# HU_SUPPORT_BOARD.net
KiCad netlist of a schematic drawn in Altium Designer
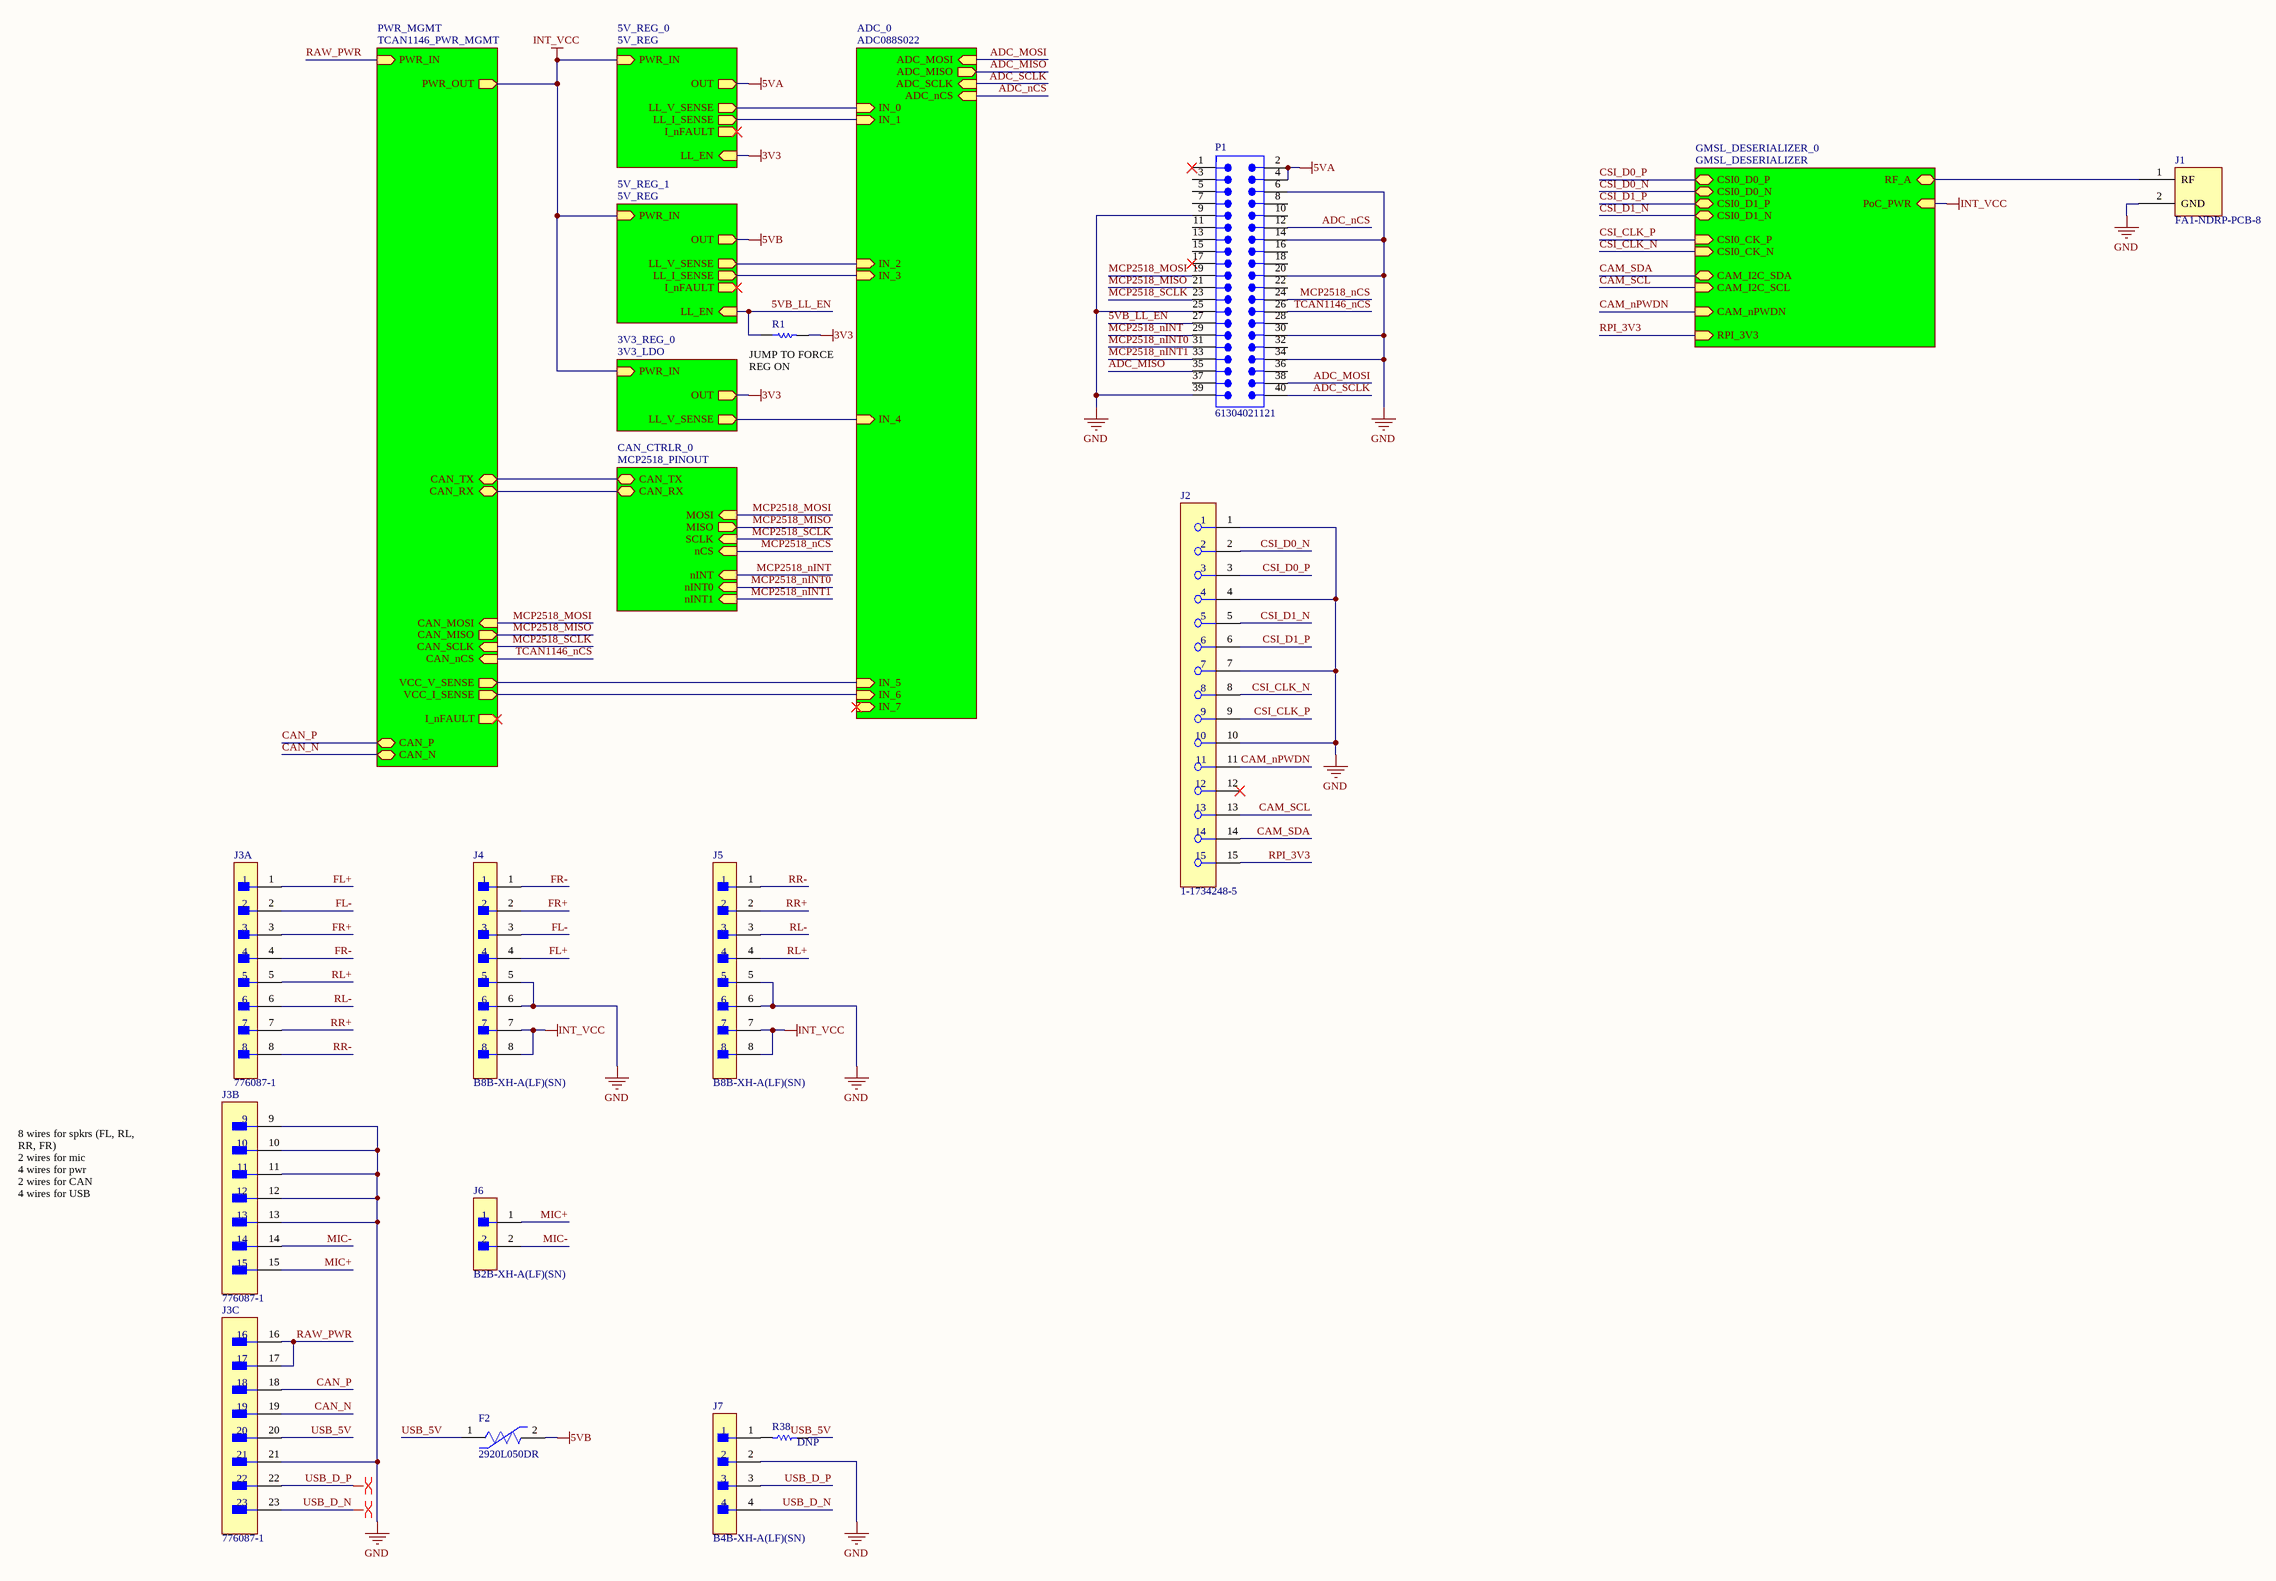
[diagram p0: HU_SUPPORT_BOARD.SchDoc]

(export (version "E")
  (design (tool "Eeschema 10.0.6"))
  (components
    (comp (ref "F2")
      (value "2920L050DR")
      (footprint "FP-2920L050DR-MFG")
      (description "PTC RESET FUSE 60V 500MA 2920")
      (libsource (lib "Altium Content Vault") (part "1c6d77a0208143737455a0c7eb396be"))
    )
    (comp (ref "J1")
      (value "FA1-NDRP-PCB-8")
      (footprint "FA1-NDRP-PCB-8-Footprint-1")
      (description "RF F Connector, Male, Board Mount, Solder Terminal, Plug")
      (libsource (lib "Space Concordia") (part "FA1-NDRP-PCB-8"))
    )
    (comp (ref "J2")
      (value "1-1734248-5")
      (footprint "FP-1-1734248-5-MFG")
      (description "CONN FPC VERT 15POS 1.00MM SMD")
      (fields
        (field (name "MANUFACTURER") "TE")
        (field (name "OCTOPART") "https://octopart.com/1-1734248-5-te+connectivity-40620898")
      )
      (libsource (lib "Altium Content Vault") (part "a0777be16b290adccad2a8f9338c195"))
    )
    (comp (ref "J3")
      (value "776087-1")
      (footprint "FP-776087-1-MFG")
      (description "CONN HEADER R/A 23POS 4MM")
      (libsource (lib "Altium Content Vault") (part "1cdbe6524175775e54446a79a4f0ed8"))
    )
    (comp (ref "J4")
      (value "B8B-XH-A(LF)(SN)")
      (footprint "FP-B8B-XH-A_LF_SN-MFG")
      (description "CONN HEADER VERT 8POS 2.5MM")
      (libsource (lib "Altium Content Vault") (part "99ec2b232beb5d2356d4d77f6a047f0"))
    )
    (comp (ref "J5")
      (value "B8B-XH-A(LF)(SN)")
      (footprint "FP-B8B-XH-A_LF_SN-MFG")
      (description "CONN HEADER VERT 8POS 2.5MM")
      (libsource (lib "Altium Content Vault") (part "99ec2b232beb5d2356d4d77f6a047f0"))
    )
    (comp (ref "J6")
      (value "B2B-XH-A(LF)(SN)")
      (footprint "FP-B2B-XH-A_LF_SN-MFG")
      (description "CONN HEADER VERT 2POS 2.5MM")
      (libsource (lib "Altium Content Vault") (part "3bc925449376181038e59eaffc5286c"))
    )
    (comp (ref "J7")
      (value "B4B-XH-A(LF)(SN)")
      (footprint "FP-B4B-XH-A_LF_SN-MFG")
      (description "CONN HEADER VERT 4POS 2.5MM")
      (libsource (lib "Altium Content Vault") (part "299a8cea1bdcbc3624fe62c390fa72c"))
    )
    (comp (ref "P1")
      (value "61304021121")
      (footprint "61304021121")
      (libsource (lib "Altium Content Vault") (part "Header_Male_2R_40P"))
    )
    (comp (ref "R1")
      (value "DNP")
      (footprint "RESC1005X40X25ML05T05")
      (description "READ THE NAME")
      (libsource (lib "Space Concordia") (part "CMP-009-00206-2"))
    )
    (comp (ref "R38")
      (value "DNP")
      (footprint "R0603B")
      (description "Resistor")
      (libsource (lib "Space Concordia") (part "Resistor"))
    )
  )
  (nets
    (net (code "1") (name "/5VB_LL_EN") (class "Default")
      (node (ref "P1") (pin "27") (pinfunction "27_27") (pintype "passive"))
      (node (ref "R1") (pin "1") (pinfunction "1_1") (pintype "passive"))
    )
    (net (code "2") (name "/ADC_MISO") (class "Default")
      (node (ref "P1") (pin "35") (pinfunction "35_35") (pintype "passive"))
    )
    (net (code "3") (name "/ADC_MOSI") (class "Default")
      (node (ref "P1") (pin "38") (pinfunction "38_38") (pintype "passive"))
    )
    (net (code "4") (name "/ADC_SCLK") (class "Default")
      (node (ref "P1") (pin "40") (pinfunction "40_40") (pintype "passive"))
    )
    (net (code "5") (name "/ADC_nCS") (class "Default")
      (node (ref "P1") (pin "12") (pinfunction "12_12") (pintype "passive"))
    )
    (net (code "6") (name "/CAM_SCL") (class "Default")
      (node (ref "J2") (pin "13") (pinfunction "13_13") (pintype "passive"))
    )
    (net (code "7") (name "/CAM_SDA") (class "Default")
      (node (ref "J2") (pin "14") (pinfunction "14_14") (pintype "passive"))
    )
    (net (code "8") (name "/CAM_nPWDN") (class "Default")
      (node (ref "J2") (pin "11") (pinfunction "11_11") (pintype "passive"))
    )
    (net (code "9") (name "/CAN_N") (class "Default")
      (node (ref "J3") (pin "19") (pinfunction "19_19") (pintype "passive"))
    )
    (net (code "10") (name "/CAN_P") (class "Default")
      (node (ref "J3") (pin "18") (pinfunction "18_18") (pintype "passive"))
    )
    (net (code "13") (name "/CSI_CLK_N") (class "Default")
      (node (ref "J2") (pin "8") (pinfunction "8_8") (pintype "passive"))
    )
    (net (code "14") (name "/CSI_CLK_P") (class "Default")
      (node (ref "J2") (pin "9") (pinfunction "9_9") (pintype "passive"))
    )
    (net (code "15") (name "/CSI_D0_N") (class "Default")
      (node (ref "J2") (pin "2") (pinfunction "2_2") (pintype "passive"))
    )
    (net (code "16") (name "/CSI_D0_P") (class "Default")
      (node (ref "J2") (pin "3") (pinfunction "3_3") (pintype "passive"))
    )
    (net (code "17") (name "/CSI_D1_N") (class "Default")
      (node (ref "J2") (pin "5") (pinfunction "5_5") (pintype "passive"))
    )
    (net (code "18") (name "/CSI_D1_P") (class "Default")
      (node (ref "J2") (pin "6") (pinfunction "6_6") (pintype "passive"))
    )
    (net (code "19") (name "/FL+") (class "Default")
      (node (ref "J3") (pin "1") (pinfunction "1_1") (pintype "passive"))
      (node (ref "J4") (pin "4") (pinfunction "4_4") (pintype "passive"))
    )
    (net (code "20") (name "/FL-") (class "Default")
      (node (ref "J3") (pin "2") (pinfunction "2_2") (pintype "passive"))
      (node (ref "J4") (pin "3") (pinfunction "3_3") (pintype "passive"))
    )
    (net (code "21") (name "/FR+") (class "Default")
      (node (ref "J3") (pin "3") (pinfunction "3_3") (pintype "passive"))
      (node (ref "J4") (pin "2") (pinfunction "2_2") (pintype "passive"))
    )
    (net (code "22") (name "/FR-") (class "Default")
      (node (ref "J3") (pin "4") (pinfunction "4_4") (pintype "passive"))
      (node (ref "J4") (pin "1") (pinfunction "1_1") (pintype "passive"))
    )
    (net (code "32") (name "/MCP2518_MISO") (class "Default")
      (node (ref "P1") (pin "21") (pinfunction "21_21") (pintype "passive"))
    )
    (net (code "33") (name "/MCP2518_MOSI") (class "Default")
      (node (ref "P1") (pin "19") (pinfunction "19_19") (pintype "passive"))
    )
    (net (code "34") (name "/MCP2518_SCLK") (class "Default")
      (node (ref "P1") (pin "23") (pinfunction "23_23") (pintype "passive"))
    )
    (net (code "35") (name "/MCP2518_nCS") (class "Default")
      (node (ref "P1") (pin "24") (pinfunction "24_24") (pintype "passive"))
    )
    (net (code "36") (name "/MCP2518_nINT") (class "Default")
      (node (ref "P1") (pin "29") (pinfunction "29_29") (pintype "passive"))
    )
    (net (code "37") (name "/MCP2518_nINT0") (class "Default")
      (node (ref "P1") (pin "31") (pinfunction "31_31") (pintype "passive"))
    )
    (net (code "38") (name "/MCP2518_nINT1") (class "Default")
      (node (ref "P1") (pin "33") (pinfunction "33_33") (pintype "passive"))
    )
    (net (code "39") (name "/MIC+") (class "Default")
      (node (ref "J3") (pin "15") (pinfunction "15_15") (pintype "passive"))
      (node (ref "J6") (pin "1") (pinfunction "1_1") (pintype "passive"))
    )
    (net (code "40") (name "/MIC-") (class "Default")
      (node (ref "J3") (pin "14") (pinfunction "14_14") (pintype "passive"))
      (node (ref "J6") (pin "2") (pinfunction "2_2") (pintype "passive"))
    )
    (net (code "41") (name "/RAW_PWR") (class "Default")
      (node (ref "J3") (pin "16") (pinfunction "16_16") (pintype "passive"))
      (node (ref "J3") (pin "17") (pinfunction "17_17") (pintype "passive"))
    )
    (net (code "42") (name "/RF_A") (class "Default")
      (node (ref "J1") (pin "1") (pinfunction "RF_1") (pintype "passive"))
    )
    (net (code "43") (name "/RL+") (class "Default")
      (node (ref "J3") (pin "5") (pinfunction "5_5") (pintype "passive"))
      (node (ref "J5") (pin "4") (pinfunction "4_4") (pintype "passive"))
    )
    (net (code "44") (name "/RL-") (class "Default")
      (node (ref "J3") (pin "6") (pinfunction "6_6") (pintype "passive"))
      (node (ref "J5") (pin "3") (pinfunction "3_3") (pintype "passive"))
    )
    (net (code "45") (name "/RPI_3V3") (class "Default")
      (node (ref "J2") (pin "15") (pinfunction "15_15") (pintype "passive"))
    )
    (net (code "46") (name "/RR+") (class "Default")
      (node (ref "J3") (pin "7") (pinfunction "7_7") (pintype "passive"))
      (node (ref "J5") (pin "2") (pinfunction "2_2") (pintype "passive"))
    )
    (net (code "47") (name "/RR-") (class "Default")
      (node (ref "J3") (pin "8") (pinfunction "8_8") (pintype "passive"))
      (node (ref "J5") (pin "1") (pinfunction "1_1") (pintype "passive"))
    )
    (net (code "48") (name "/TCAN1146_nCS") (class "Default")
      (node (ref "P1") (pin "26") (pinfunction "26_26") (pintype "passive"))
    )
    (net (code "49") (name "/USB_5V") (class "Default")
      (node (ref "F2") (pin "1") (pinfunction "1_1") (pintype "passive"))
      (node (ref "J3") (pin "20") (pinfunction "20_20") (pintype "passive"))
      (node (ref "R38") (pin "1") (pinfunction "1_1") (pintype "passive"))
    )
    (net (code "50") (name "/USB_D_N") (class "Default")
      (node (ref "J3") (pin "23") (pinfunction "23_23") (pintype "passive"))
      (node (ref "J7") (pin "4") (pinfunction "4_4") (pintype "passive"))
    )
    (net (code "51") (name "/USB_D_P") (class "Default")
      (node (ref "J3") (pin "22") (pinfunction "22_22") (pintype "passive"))
      (node (ref "J7") (pin "3") (pinfunction "3_3") (pintype "passive"))
    )
    (net (code "54") (name "3V3") (class "Default")
      (node (ref "R1") (pin "2") (pinfunction "2_2") (pintype "passive"))
    )
    (net (code "55") (name "5VA") (class "Default")
      (node (ref "P1") (pin "2") (pinfunction "2_2") (pintype "passive"))
      (node (ref "P1") (pin "4") (pinfunction "4_4") (pintype "passive"))
    )
    (net (code "56") (name "5VB") (class "Default")
      (node (ref "F2") (pin "2") (pinfunction "2_2") (pintype "passive"))
    )
    (net (code "57") (name "GND") (class "Default")
      (node (ref "J1") (pin "2") (pinfunction "GND_2") (pintype "passive"))
      (node (ref "J2") (pin "1") (pinfunction "1_1") (pintype "passive"))
      (node (ref "J2") (pin "10") (pinfunction "10_10") (pintype "passive"))
      (node (ref "J2") (pin "4") (pinfunction "4_4") (pintype "passive"))
      (node (ref "J2") (pin "7") (pinfunction "7_7") (pintype "passive"))
      (node (ref "J3") (pin "10") (pinfunction "10_10") (pintype "passive"))
      (node (ref "J3") (pin "11") (pinfunction "11_11") (pintype "passive"))
      (node (ref "J3") (pin "12") (pinfunction "12_12") (pintype "passive"))
      (node (ref "J3") (pin "13") (pinfunction "13_13") (pintype "passive"))
      (node (ref "J3") (pin "21") (pinfunction "21_21") (pintype "passive"))
      (node (ref "J3") (pin "9") (pinfunction "9_9") (pintype "passive"))
      (node (ref "J4") (pin "5") (pinfunction "5_5") (pintype "passive"))
      (node (ref "J4") (pin "6") (pinfunction "6_6") (pintype "passive"))
      (node (ref "J5") (pin "5") (pinfunction "5_5") (pintype "passive"))
      (node (ref "J5") (pin "6") (pinfunction "6_6") (pintype "passive"))
      (node (ref "J7") (pin "2") (pinfunction "2_2") (pintype "passive"))
      (node (ref "P1") (pin "14") (pinfunction "14_14") (pintype "passive"))
      (node (ref "P1") (pin "20") (pinfunction "20_20") (pintype "passive"))
      (node (ref "P1") (pin "25") (pinfunction "25_25") (pintype "passive"))
      (node (ref "P1") (pin "30") (pinfunction "30_30") (pintype "passive"))
      (node (ref "P1") (pin "34") (pinfunction "34_34") (pintype "passive"))
      (node (ref "P1") (pin "39") (pinfunction "39_39") (pintype "passive"))
      (node (ref "P1") (pin "6") (pinfunction "6_6") (pintype "passive"))
      (node (ref "P1") (pin "9") (pinfunction "9_9") (pintype "passive"))
    )
    (net (code "58") (name "INT_VCC") (class "Default")
      (node (ref "J4") (pin "7") (pinfunction "7_7") (pintype "passive"))
      (node (ref "J4") (pin "8") (pinfunction "8_8") (pintype "passive"))
      (node (ref "J5") (pin "7") (pinfunction "7_7") (pintype "passive"))
      (node (ref "J5") (pin "8") (pinfunction "8_8") (pintype "passive"))
    )
    (net (code "59") (name "Net-(J7-Pad1)") (class "Default")
      (node (ref "J7") (pin "1") (pinfunction "1_1") (pintype "passive"))
      (node (ref "R38") (pin "2") (pinfunction "2_2") (pintype "passive"))
    )
    (net (code "60") (name "unconnected-(J2-Pad12)") (class "Default")
      (node (ref "J2") (pin "12") (pinfunction "12_12") (pintype "passive+no_connect"))
    )
    (net (code "61") (name "unconnected-(P1-Pad1)") (class "Default")
      (node (ref "P1") (pin "1") (pinfunction "1_1") (pintype "passive+no_connect"))
    )
    (net (code "62") (name "unconnected-(P1-Pad3)") (class "Default")
      (node (ref "P1") (pin "3") (pinfunction "3_3") (pintype "passive"))
    )
    (net (code "63") (name "unconnected-(P1-Pad5)") (class "Default")
      (node (ref "P1") (pin "5") (pinfunction "5_5") (pintype "passive"))
    )
    (net (code "64") (name "unconnected-(P1-Pad7)") (class "Default")
      (node (ref "P1") (pin "7") (pinfunction "7_7") (pintype "passive"))
    )
    (net (code "65") (name "unconnected-(P1-Pad8)") (class "Default")
      (node (ref "P1") (pin "8") (pinfunction "8_8") (pintype "passive"))
    )
    (net (code "66") (name "unconnected-(P1-Pad10)") (class "Default")
      (node (ref "P1") (pin "10") (pinfunction "10_10") (pintype "passive"))
    )
    (net (code "67") (name "unconnected-(P1-Pad11)") (class "Default")
      (node (ref "P1") (pin "11") (pinfunction "11_11") (pintype "passive"))
    )
    (net (code "68") (name "unconnected-(P1-Pad13)") (class "Default")
      (node (ref "P1") (pin "13") (pinfunction "13_13") (pintype "passive"))
    )
    (net (code "69") (name "unconnected-(P1-Pad15)") (class "Default")
      (node (ref "P1") (pin "15") (pinfunction "15_15") (pintype "passive"))
    )
    (net (code "70") (name "unconnected-(P1-Pad16)") (class "Default")
      (node (ref "P1") (pin "16") (pinfunction "16_16") (pintype "passive"))
    )
    (net (code "71") (name "unconnected-(P1-Pad17)") (class "Default")
      (node (ref "P1") (pin "17") (pinfunction "17_17") (pintype "passive+no_connect"))
    )
    (net (code "72") (name "unconnected-(P1-Pad18)") (class "Default")
      (node (ref "P1") (pin "18") (pinfunction "18_18") (pintype "passive"))
    )
    (net (code "73") (name "unconnected-(P1-Pad22)") (class "Default")
      (node (ref "P1") (pin "22") (pinfunction "22_22") (pintype "passive"))
    )
    (net (code "74") (name "unconnected-(P1-Pad28)") (class "Default")
      (node (ref "P1") (pin "28") (pinfunction "28_28") (pintype "passive"))
    )
    (net (code "75") (name "unconnected-(P1-Pad32)") (class "Default")
      (node (ref "P1") (pin "32") (pinfunction "32_32") (pintype "passive"))
    )
    (net (code "76") (name "unconnected-(P1-Pad36)") (class "Default")
      (node (ref "P1") (pin "36") (pinfunction "36_36") (pintype "passive"))
    )
    (net (code "77") (name "unconnected-(P1-Pad37)") (class "Default")
      (node (ref "P1") (pin "37") (pinfunction "37_37") (pintype "passive"))
    )
  )
)
